# Half_Slave.net
KiCad netlist of a schematic drawn in Altium Designer
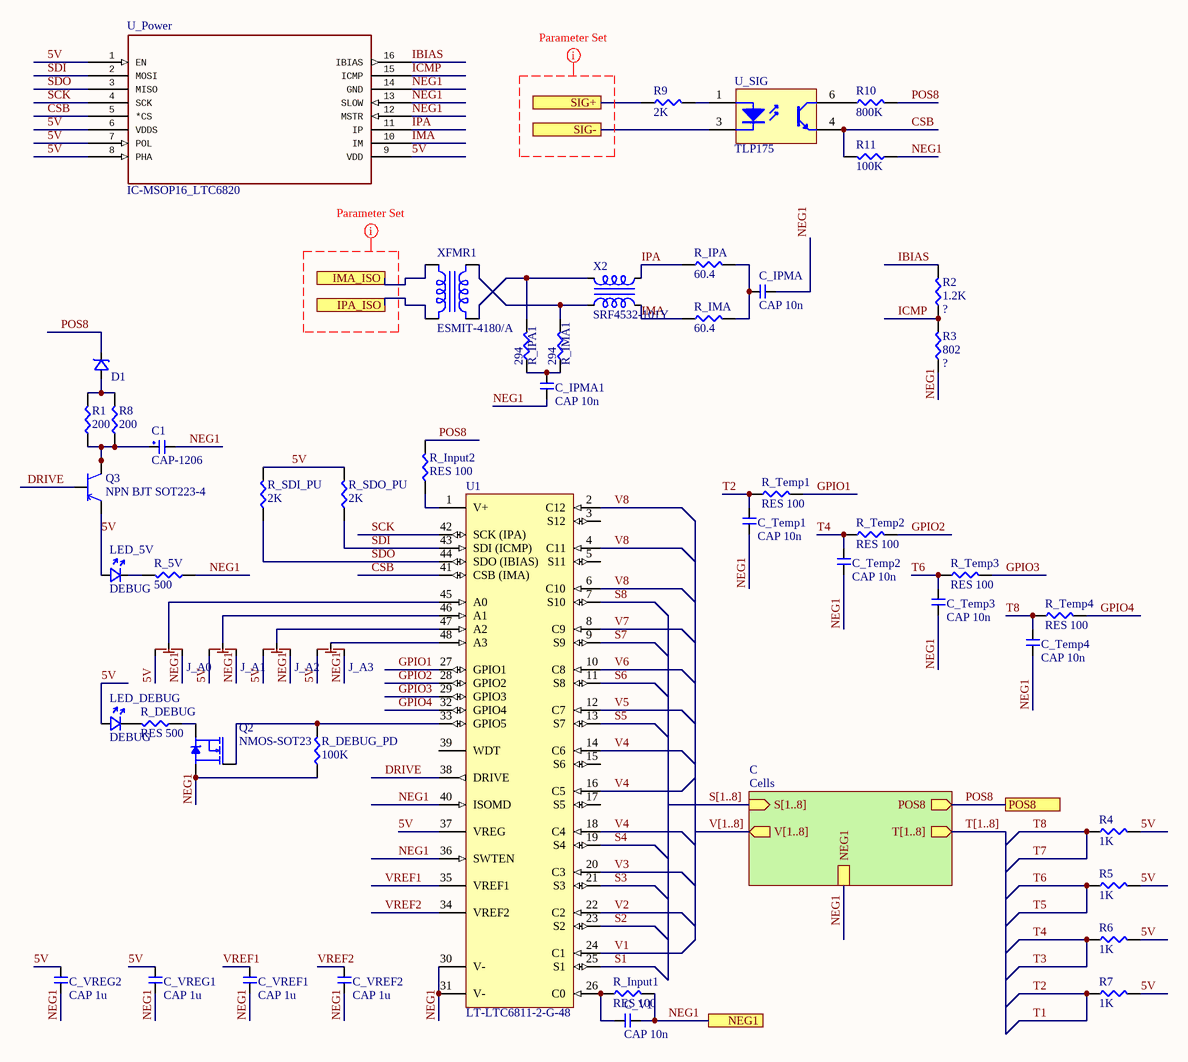
[diagram p0: Half_Slave.SchDoc]

(export (version "E")
  (design (tool "Eeschema 10.0.6"))
  (components
    (comp (ref "C1")
      (value "CAP-1206")
      (footprint "CAPCP3216X16N")
      (libsource (lib "LTC6811") (part "CAP-1206"))
    )
    (comp (ref "C_IPMA")
      (value "CAP 10n")
      (footprint "CAP-0603")
      (description "CAP-0603")
      (libsource (lib "ife18_TS_BMS_LTC6813_v2_Library") (part "CAP-0603"))
    )
    (comp (ref "C_IPMA1")
      (value "CAP 10n")
      (footprint "CAP-0603")
      (description "CAP-0603")
      (libsource (lib "ife18_TS_BMS_LTC6813_v2_Library") (part "CAP-0603"))
    )
    (comp (ref "C_Temp1")
      (value "CAP 10n")
      (footprint "CAP-0603")
      (description "CAP-0603")
      (libsource (lib "altium-import") (part "root_1_CAP-0603_"))
    )
    (comp (ref "C_Temp2")
      (value "CAP 10n")
      (footprint "CAP-0603")
      (description "CAP-0603")
      (libsource (lib "altium-import") (part "root_1_CAP-0603_"))
    )
    (comp (ref "C_Temp3")
      (value "CAP 10n")
      (footprint "CAP-0603")
      (description "CAP-0603")
      (libsource (lib "altium-import") (part "root_1_CAP-0603_"))
    )
    (comp (ref "C_Temp4")
      (value "CAP 10n")
      (footprint "CAP-0603")
      (description "CAP-0603")
      (libsource (lib "altium-import") (part "root_1_CAP-0603_"))
    )
    (comp (ref "C_V1")
      (value "CAP 10n")
      (footprint "CAP-0603")
      (description "CAP-0603")
      (libsource (lib "altium-import") (part "root_2_CAP-0603_"))
    )
    (comp (ref "C_VREF1")
      (value "CAP 1u")
      (footprint "CAP-0603")
      (description "CAP-0603")
      (libsource (lib "altium-import") (part "root_1_CAP-0603_"))
    )
    (comp (ref "C_VREF2")
      (value "CAP 1u")
      (footprint "CAP-0603")
      (description "CAP-0603")
      (libsource (lib "altium-import") (part "root_1_CAP-0603_"))
    )
    (comp (ref "C_VREG1")
      (value "CAP 1u")
      (footprint "CAP-0603")
      (description "CAP-0603")
      (libsource (lib "altium-import") (part "root_1_CAP-0603_"))
    )
    (comp (ref "C_VREG2")
      (value "CAP 1u")
      (footprint "CAP-0603")
      (description "CAP-0603")
      (libsource (lib "altium-import") (part "root_1_CAP-0603_"))
    )
    (comp (ref "D1") (value "?") (footprint "SMB") (libsource (lib "ife19_Elec_Library") (part "DIODE-SMB")))
    (comp (ref "J_A0")
      (value "DPDT Solder Jumper")
      (footprint "DPDT Solder")
      (libsource (lib "LTC6811") (part "DPDT Solder"))
    )
    (comp (ref "J_A1")
      (value "DPDT Solder Jumper")
      (footprint "DPDT Solder")
      (libsource (lib "LTC6811") (part "DPDT Solder"))
    )
    (comp (ref "J_A2")
      (value "DPDT Solder Jumper")
      (footprint "DPDT Solder")
      (libsource (lib "LTC6811") (part "DPDT Solder"))
    )
    (comp (ref "J_A3")
      (value "DPDT Solder Jumper")
      (footprint "DPDT Solder")
      (libsource (lib "LTC6811") (part "DPDT Solder"))
    )
    (comp (ref "LED_5V")
      (value "DEBUG")
      (footprint "LED-0603")
      (description "LED-0603")
      (libsource (lib "altium-import") (part "root_0_LED-0603_"))
    )
    (comp (ref "LED_DEBUG")
      (value "DEBUG")
      (footprint "LED-0603")
      (description "LED-0603")
      (libsource (lib "altium-import") (part "root_0_LED-0603_"))
    )
    (comp (ref "Q2")
      (value "NMOS-SOT23")
      (footprint "SOT23")
      (libsource (lib "ife19_Elec_Library") (part "NMOS-SOT23"))
    )
    (comp (ref "Q3")
      (value "NPN BJT SOT223-4")
      (footprint "SOT223")
      (description "BCP54,115")
      (libsource (lib "ife19_Elec_Library") (part "NPN_SOT223-4"))
    )
    (comp (ref "R1")
      (value "200")
      (footprint "RES-0603")
      (libsource (lib "ife18_TS_BMS_LTC6813_v2_Library") (part "RES-0603"))
    )
    (comp (ref "R2")
      (value "1.2K")
      (footprint "RES-0603")
      (description "RES SMD 0603")
      (fields (field (name "PART") "RES_0603") (field (name "ALTIUM_VALUE") "?"))
      (libsource (lib "IFE") (part "RES"))
    )
    (comp (ref "R3")
      (value "802")
      (footprint "RES-0603")
      (description "RES SMD 0603")
      (fields (field (name "PART") "RES_0603") (field (name "ALTIUM_VALUE") "?"))
      (libsource (lib "IFE") (part "RES"))
    )
    (comp (ref "R4")
      (value "1K")
      (footprint "RES-0603")
      (libsource (lib "ife19_Elec_Library") (part "RES-0603"))
    )
    (comp (ref "R5")
      (value "1K")
      (footprint "RES-0603")
      (libsource (lib "ife19_Elec_Library") (part "RES-0603"))
    )
    (comp (ref "R6")
      (value "1K")
      (footprint "RES-0603")
      (libsource (lib "ife19_Elec_Library") (part "RES-0603"))
    )
    (comp (ref "R7")
      (value "1K")
      (footprint "RES-0603")
      (libsource (lib "ife19_Elec_Library") (part "RES-0603"))
    )
    (comp (ref "R8")
      (value "200")
      (footprint "RES-0603")
      (libsource (lib "ife18_TS_BMS_LTC6813_v2_Library") (part "RES-0603"))
    )
    (comp (ref "R9")
      (value "2K")
      (footprint "RES-0603")
      (libsource (lib "ife19_Elec_Library") (part "RES-0603"))
    )
    (comp (ref "R10")
      (value "800K")
      (footprint "RES-0603")
      (libsource (lib "ife19_Elec_Library") (part "RES-0603"))
    )
    (comp (ref "R11")
      (value "100K")
      (footprint "RES-0603")
      (libsource (lib "ife19_Elec_Library") (part "RES-0603"))
    )
    (comp (ref "R_5V")
      (value "500")
      (footprint "RES-0603")
      (libsource (lib "altium-import") (part "root_2_RES-0603_"))
    )
    (comp (ref "R_DEBUG")
      (value "RES 500")
      (footprint "RES-0603")
      (libsource (lib "altium-import") (part "root_2_RES-0603_"))
    )
    (comp (ref "R_DEBUG_PD")
      (value "100K")
      (footprint "RES-0603")
      (libsource (lib "ife18_TS_BMS_LTC6813_v2_Library") (part "RES-0603"))
    )
    (comp (ref "R_IMA")
      (value "60.4")
      (footprint "RES-0603")
      (libsource (lib "ife18_TS_BMS_LTC6813_v2_Library") (part "RES-0603"))
    )
    (comp (ref "R_IMA1")
      (value "294")
      (footprint "RES-0603")
      (libsource (lib "ife18_TS_BMS_LTC6813_v2_Library") (part "RES-0603"))
    )
    (comp (ref "R_Input1")
      (value "RES 100")
      (footprint "RES-0603")
      (libsource (lib "altium-import") (part "root_0_RES-0603_"))
    )
    (comp (ref "R_Input2")
      (value "RES 100")
      (footprint "RES-0603")
      (libsource (lib "altium-import") (part "root_1_RES-0603_"))
    )
    (comp (ref "R_IPA")
      (value "60.4")
      (footprint "RES-0603")
      (libsource (lib "ife18_TS_BMS_LTC6813_v2_Library") (part "RES-0603"))
    )
    (comp (ref "R_IPA1")
      (value "294")
      (footprint "RES-0603")
      (libsource (lib "ife18_TS_BMS_LTC6813_v2_Library") (part "RES-0603"))
    )
    (comp (ref "R_SDI_PU")
      (value "2K")
      (footprint "RES-0603")
      (libsource (lib "ife18_TS_BMS_LTC6813_v2_Library") (part "RES-0603"))
    )
    (comp (ref "R_SDO_PU")
      (value "2K")
      (footprint "RES-0603")
      (libsource (lib "ife18_TS_BMS_LTC6813_v2_Library") (part "RES-0603"))
    )
    (comp (ref "R_Temp1")
      (value "RES 100")
      (footprint "RES-0603")
      (libsource (lib "altium-import") (part "root_0_RES-0603_"))
    )
    (comp (ref "R_Temp2")
      (value "RES 100")
      (footprint "RES-0603")
      (libsource (lib "altium-import") (part "root_0_RES-0603_"))
    )
    (comp (ref "R_Temp3")
      (value "RES 100")
      (footprint "RES-0603")
      (libsource (lib "altium-import") (part "root_0_RES-0603_"))
    )
    (comp (ref "R_Temp4")
      (value "RES 100")
      (footprint "RES-0603")
      (libsource (lib "altium-import") (part "root_0_RES-0603_"))
    )
    (comp (ref "U1")
      (value "LT-LTC6811-2-G-48")
      (footprint "SSOP-48N")
      (libsource (lib "LTC6811") (part "LT-LTC6811-2-G-48"))
    )
    (comp (ref "U_Power")
      (value "IC-MSOP16_LTC6820")
      (footprint "MSOP16")
      (libsource (lib "ife19_Elec_Library") (part "IC-MSOP16_LTC6820"))
    )
    (comp (ref "U_SIG")
      (value "TLP175")
      (footprint "TOSH-11-4C1_N")
      (fields (field (name "MANUFACTURER") "Toshiba"))
      (libsource (lib "Altium Content Vault") (part "TOSH-TLP181-SOP-4"))
    )
    (comp (ref "X2")
      (value "SRF4532-101Y")
      (footprint "SRF4532")
      (libsource (lib "ife19_Elec_Library") (part "CMC_SRF4532"))
    )
    (comp (ref "XFMR1")
      (value "ESMIT-4180/A")
      (footprint "ISOXFMR_ESMIT4180")
      (libsource (lib "ife19_Elec_Library") (part "ISOXFMR_ESMIT4180"))
    )
  )
  (nets
    (net (code "1") (name "/5V") (class "Default")
      (node (ref "C_VREG1") (pin "2") (pinfunction "2_2") (pintype "passive"))
      (node (ref "C_VREG2") (pin "2") (pinfunction "2_2") (pintype "passive"))
      (node (ref "J_A0") (pin "2") (pintype "passive"))
      (node (ref "J_A1") (pin "2") (pintype "passive"))
      (node (ref "J_A2") (pin "2") (pintype "passive"))
      (node (ref "J_A3") (pin "2") (pintype "passive"))
      (node (ref "LED_5V") (pin "A") (pinfunction "A_A") (pintype "passive"))
      (node (ref "LED_DEBUG") (pin "A") (pinfunction "A_A") (pintype "passive"))
      (node (ref "Q3") (pin "3") (pinfunction "E_3") (pintype "passive"))
      (node (ref "R4") (pin "2") (pinfunction "2_2") (pintype "passive"))
      (node (ref "R5") (pin "2") (pinfunction "2_2") (pintype "passive"))
      (node (ref "R6") (pin "2") (pinfunction "2_2") (pintype "passive"))
      (node (ref "R7") (pin "2") (pinfunction "2_2") (pintype "passive"))
      (node (ref "R_SDI_PU") (pin "2") (pinfunction "2_2") (pintype "passive"))
      (node (ref "R_SDO_PU") (pin "2") (pinfunction "2_2") (pintype "passive"))
      (node (ref "U1") (pin "37") (pinfunction "VREG_37") (pintype "power_in"))
      (node (ref "U_Power") (pin "1") (pinfunction "EN_1") (pintype "input"))
      (node (ref "U_Power") (pin "6") (pinfunction "VDDS_6") (pintype "power_in"))
      (node (ref "U_Power") (pin "7") (pinfunction "POL_7") (pintype "input"))
      (node (ref "U_Power") (pin "8") (pinfunction "PHA_8") (pintype "input"))
      (node (ref "U_Power") (pin "9") (pinfunction "VDD_9") (pintype "power_in"))
    )
    (net (code "2") (name "/CSB") (class "Default")
      (node (ref "R11") (pin "2") (pinfunction "2_2") (pintype "passive"))
      (node (ref "U1") (pin "41") (pinfunction "CSB_(IMA)_41") (pintype "bidirectional"))
      (node (ref "U_Power") (pin "5") (pinfunction "*CS_5") (pintype "passive"))
      (node (ref "U_SIG") (pin "4") (pinfunction "EMITTER_4") (pintype "passive"))
    )
    (net (code "3") (name "/DRIVE") (class "Default")
      (node (ref "Q3") (pin "1") (pinfunction "B_1") (pintype "passive"))
      (node (ref "U1") (pin "38") (pinfunction "DRIVE_38") (pintype "output"))
    )
    (net (code "4") (name "/GPIO1") (class "Default")
      (node (ref "R_Temp1") (pin "2") (pinfunction "2_2") (pintype "passive"))
      (node (ref "U1") (pin "27") (pinfunction "GPIO1_27") (pintype "bidirectional"))
    )
    (net (code "5") (name "/GPIO2") (class "Default")
      (node (ref "R_Temp2") (pin "2") (pinfunction "2_2") (pintype "passive"))
      (node (ref "U1") (pin "28") (pinfunction "GPIO2_28") (pintype "bidirectional"))
    )
    (net (code "6") (name "/GPIO3") (class "Default")
      (node (ref "R_Temp3") (pin "2") (pinfunction "2_2") (pintype "passive"))
      (node (ref "U1") (pin "29") (pinfunction "GPIO3_29") (pintype "bidirectional"))
    )
    (net (code "7") (name "/GPIO4") (class "Default")
      (node (ref "R_Temp4") (pin "2") (pinfunction "2_2") (pintype "passive"))
      (node (ref "U1") (pin "32") (pinfunction "GPIO4_32") (pintype "bidirectional"))
    )
    (net (code "8") (name "/IBIAS") (class "Default")
      (node (ref "R2") (pin "2") (pinfunction "2_2") (pintype "passive"))
      (node (ref "U_Power") (pin "16") (pinfunction "IBIAS_16") (pintype "output"))
    )
    (net (code "9") (name "/ICMP") (class "Default")
      (node (ref "R2") (pin "1") (pinfunction "1_1") (pintype "passive"))
      (node (ref "R3") (pin "2") (pinfunction "2_2") (pintype "passive"))
      (node (ref "U_Power") (pin "15") (pinfunction "ICMP_15") (pintype "passive"))
    )
    (net (code "10") (name "/IMA") (class "Default")
      (node (ref "R_IMA") (pin "2") (pinfunction "2_2") (pintype "passive"))
      (node (ref "U_Power") (pin "10") (pinfunction "IM_10") (pintype "passive"))
      (node (ref "X2") (pin "4") (pinfunction "4_4") (pintype "passive"))
    )
    (net (code "11") (name "/IMA_ISO") (class "Default")
      (node (ref "XFMR1") (pin "2") (pinfunction "2_2") (pintype "passive"))
    )
    (net (code "12") (name "/IPA") (class "Default")
      (node (ref "R_IPA") (pin "2") (pinfunction "2_2") (pintype "passive"))
      (node (ref "U_Power") (pin "11") (pinfunction "IP_11") (pintype "passive"))
      (node (ref "X2") (pin "1") (pinfunction "1_1") (pintype "passive"))
    )
    (net (code "13") (name "/IPA_ISO") (class "Default")
      (node (ref "XFMR1") (pin "1") (pinfunction "1_1") (pintype "passive"))
    )
    (net (code "14") (name "/NEG1") (class "Default")
      (node (ref "C1") (pin "2") (pinfunction "2_2") (pintype "passive"))
      (node (ref "C_IPMA") (pin "1") (pinfunction "1_1") (pintype "passive"))
      (node (ref "C_IPMA1") (pin "1") (pinfunction "1_1") (pintype "passive"))
      (node (ref "C_Temp1") (pin "1") (pinfunction "1_1") (pintype "passive"))
      (node (ref "C_Temp2") (pin "1") (pinfunction "1_1") (pintype "passive"))
      (node (ref "C_Temp3") (pin "1") (pinfunction "1_1") (pintype "passive"))
      (node (ref "C_Temp4") (pin "1") (pinfunction "1_1") (pintype "passive"))
      (node (ref "C_V1") (pin "1") (pinfunction "1_1") (pintype "passive"))
      (node (ref "C_VREF1") (pin "1") (pinfunction "1_1") (pintype "passive"))
      (node (ref "C_VREF2") (pin "1") (pinfunction "1_1") (pintype "passive"))
      (node (ref "C_VREG1") (pin "1") (pinfunction "1_1") (pintype "passive"))
      (node (ref "C_VREG2") (pin "1") (pinfunction "1_1") (pintype "passive"))
      (node (ref "J_A0") (pin "1") (pintype "passive"))
      (node (ref "J_A1") (pin "1") (pintype "passive"))
      (node (ref "J_A2") (pin "1") (pintype "passive"))
      (node (ref "J_A3") (pin "1") (pintype "passive"))
      (node (ref "Q2") (pin "2") (pinfunction "S_2") (pintype "passive"))
      (node (ref "R11") (pin "1") (pinfunction "1_1") (pintype "passive"))
      (node (ref "R3") (pin "1") (pinfunction "1_1") (pintype "passive"))
      (node (ref "R_5V") (pin "1") (pinfunction "1_1") (pintype "passive"))
      (node (ref "R_DEBUG_PD") (pin "1") (pinfunction "1_1") (pintype "passive"))
      (node (ref "R_Input1") (pin "2") (pinfunction "2_2") (pintype "passive"))
      (node (ref "U1") (pin "30") (pinfunction "V-_30") (pintype "power_in"))
      (node (ref "U1") (pin "31") (pinfunction "V-_31") (pintype "power_in"))
      (node (ref "U1") (pin "36") (pinfunction "SWTEN_36") (pintype "input"))
      (node (ref "U1") (pin "40") (pinfunction "ISOMD_40") (pintype "input"))
      (node (ref "U_Power") (pin "12") (pinfunction "MSTR_12") (pintype "input"))
      (node (ref "U_Power") (pin "13") (pinfunction "SLOW_13") (pintype "input"))
      (node (ref "U_Power") (pin "14") (pinfunction "GND_14") (pintype "power_in"))
    )
    (net (code "15") (name "/POS8") (class "Default")
      (node (ref "D1") (pin "K") (pinfunction "K_K") (pintype "passive"))
      (node (ref "R10") (pin "2") (pinfunction "2_2") (pintype "passive"))
      (node (ref "R_Input2") (pin "2") (pinfunction "2_2") (pintype "passive"))
    )
    (net (code "16") (name "/S1") (class "Default")
      (node (ref "U1") (pin "25") (pinfunction "S1_25") (pintype "bidirectional"))
    )
    (net (code "17") (name "/S2") (class "Default")
      (node (ref "U1") (pin "23") (pinfunction "S2_23") (pintype "bidirectional"))
    )
    (net (code "18") (name "/S3") (class "Default")
      (node (ref "U1") (pin "21") (pinfunction "S3_21") (pintype "bidirectional"))
    )
    (net (code "19") (name "/S4") (class "Default")
      (node (ref "U1") (pin "19") (pinfunction "S4_19") (pintype "bidirectional"))
    )
    (net (code "20") (name "/S5") (class "Default")
      (node (ref "U1") (pin "13") (pinfunction "S7_13") (pintype "bidirectional"))
    )
    (net (code "21") (name "/S6") (class "Default")
      (node (ref "U1") (pin "11") (pinfunction "S8_11") (pintype "bidirectional"))
    )
    (net (code "22") (name "/S7") (class "Default")
      (node (ref "U1") (pin "9") (pinfunction "S9_9") (pintype "bidirectional"))
    )
    (net (code "23") (name "/S8") (class "Default")
      (node (ref "U1") (pin "7") (pinfunction "S10_7") (pintype "bidirectional"))
    )
    (net (code "24") (name "/SCK") (class "Default")
      (node (ref "U1") (pin "42") (pinfunction "SCK_(IPA)_42") (pintype "bidirectional"))
      (node (ref "U_Power") (pin "4") (pinfunction "SCK_4") (pintype "passive"))
    )
    (net (code "25") (name "/SDI") (class "Default")
      (node (ref "R_SDO_PU") (pin "1") (pinfunction "1_1") (pintype "passive"))
      (node (ref "U1") (pin "43") (pinfunction "SDI_(ICMP)_43") (pintype "input"))
      (node (ref "U_Power") (pin "2") (pinfunction "MOSI_2") (pintype "passive"))
    )
    (net (code "26") (name "/SDO") (class "Default")
      (node (ref "R_SDI_PU") (pin "1") (pinfunction "1_1") (pintype "passive"))
      (node (ref "U1") (pin "44") (pinfunction "SDO_(IBIAS)_44") (pintype "bidirectional"))
      (node (ref "U_Power") (pin "3") (pinfunction "MISO_3") (pintype "passive"))
    )
    (net (code "27") (name "/SIG+") (class "Default")
      (node (ref "R9") (pin "1") (pinfunction "1_1") (pintype "passive"))
    )
    (net (code "28") (name "/SIG-") (class "Default")
      (node (ref "U_SIG") (pin "3") (pinfunction "CATHODE_3") (pintype "passive"))
    )
    (net (code "30") (name "/T2") (class "Default")
      (node (ref "C_Temp1") (pin "2") (pinfunction "2_2") (pintype "passive"))
      (node (ref "R7") (pin "1") (pinfunction "1_1") (pintype "passive"))
      (node (ref "R_Temp1") (pin "1") (pinfunction "1_1") (pintype "passive"))
    )
    (net (code "31") (name "/T4") (class "Default")
      (node (ref "C_Temp2") (pin "2") (pinfunction "2_2") (pintype "passive"))
      (node (ref "R6") (pin "1") (pinfunction "1_1") (pintype "passive"))
      (node (ref "R_Temp2") (pin "1") (pinfunction "1_1") (pintype "passive"))
    )
    (net (code "32") (name "/T6") (class "Default")
      (node (ref "C_Temp3") (pin "2") (pinfunction "2_2") (pintype "passive"))
      (node (ref "R5") (pin "1") (pinfunction "1_1") (pintype "passive"))
      (node (ref "R_Temp3") (pin "1") (pinfunction "1_1") (pintype "passive"))
    )
    (net (code "33") (name "/T8") (class "Default")
      (node (ref "C_Temp4") (pin "2") (pinfunction "2_2") (pintype "passive"))
      (node (ref "R4") (pin "1") (pinfunction "1_1") (pintype "passive"))
      (node (ref "R_Temp4") (pin "1") (pinfunction "1_1") (pintype "passive"))
    )
    (net (code "35") (name "/V1") (class "Default")
      (node (ref "U1") (pin "24") (pinfunction "C1_24") (pintype "input"))
    )
    (net (code "36") (name "/V2") (class "Default")
      (node (ref "U1") (pin "22") (pinfunction "C2_22") (pintype "input"))
    )
    (net (code "37") (name "/V3") (class "Default")
      (node (ref "U1") (pin "20") (pinfunction "C3_20") (pintype "input"))
    )
    (net (code "38") (name "/V4") (class "Default")
      (node (ref "U1") (pin "14") (pinfunction "C6_14") (pintype "input"))
      (node (ref "U1") (pin "16") (pinfunction "C5_16") (pintype "input"))
      (node (ref "U1") (pin "18") (pinfunction "C4_18") (pintype "input"))
    )
    (net (code "39") (name "/V5") (class "Default")
      (node (ref "U1") (pin "12") (pinfunction "C7_12") (pintype "input"))
    )
    (net (code "40") (name "/V6") (class "Default")
      (node (ref "U1") (pin "10") (pinfunction "C8_10") (pintype "input"))
    )
    (net (code "41") (name "/V7") (class "Default")
      (node (ref "U1") (pin "8") (pinfunction "C9_8") (pintype "input"))
    )
    (net (code "42") (name "/V8") (class "Default")
      (node (ref "U1") (pin "2") (pinfunction "C12_2") (pintype "input"))
      (node (ref "U1") (pin "4") (pinfunction "C11_4") (pintype "input"))
      (node (ref "U1") (pin "6") (pinfunction "C10_6") (pintype "input"))
    )
    (net (code "43") (name "/VREF1") (class "Default")
      (node (ref "C_VREF1") (pin "2") (pinfunction "2_2") (pintype "passive"))
      (node (ref "U1") (pin "35") (pinfunction "VREF1_35") (pintype "passive"))
    )
    (net (code "44") (name "/VREF2") (class "Default")
      (node (ref "C_VREF2") (pin "2") (pinfunction "2_2") (pintype "passive"))
      (node (ref "U1") (pin "34") (pinfunction "VREF2_34") (pintype "passive"))
    )
    (net (code "46") (name "Net-(C1-Pad1)") (class "Default")
      (node (ref "C1") (pin "1") (pinfunction "1_1") (pintype "passive"))
      (node (ref "Q3") (pin "2") (pinfunction "C_2") (pintype "passive"))
      (node (ref "Q3") (pin "4") (pinfunction "C_4") (pintype "passive"))
      (node (ref "R1") (pin "1") (pinfunction "1_1") (pintype "passive"))
      (node (ref "R8") (pin "1") (pinfunction "1_1") (pintype "passive"))
    )
    (net (code "47") (name "Net-(C_IPMA-Pad2)") (class "Default")
      (node (ref "C_IPMA") (pin "2") (pinfunction "2_2") (pintype "passive"))
      (node (ref "R_IMA") (pin "1") (pinfunction "1_1") (pintype "passive"))
      (node (ref "R_IPA") (pin "1") (pinfunction "1_1") (pintype "passive"))
    )
    (net (code "48") (name "Net-(C_IPMA1-Pad2)") (class "Default")
      (node (ref "C_IPMA1") (pin "2") (pinfunction "2_2") (pintype "passive"))
      (node (ref "R_IMA1") (pin "1") (pinfunction "1_1") (pintype "passive"))
      (node (ref "R_IPA1") (pin "1") (pinfunction "1_1") (pintype "passive"))
    )
    (net (code "49") (name "Net-(D1-PadA)") (class "Default")
      (node (ref "D1") (pin "A") (pinfunction "A_A") (pintype "passive"))
      (node (ref "R1") (pin "2") (pinfunction "2_2") (pintype "passive"))
      (node (ref "R8") (pin "2") (pinfunction "2_2") (pintype "passive"))
    )
    (net (code "50") (name "Net-(LED_5V-PadK)") (class "Default")
      (node (ref "LED_5V") (pin "K") (pinfunction "K_K") (pintype "passive"))
      (node (ref "R_5V") (pin "2") (pinfunction "2_2") (pintype "passive"))
    )
    (net (code "51") (name "Net-(LED_DEBUG-PadK)") (class "Default")
      (node (ref "LED_DEBUG") (pin "K") (pinfunction "K_K") (pintype "passive"))
      (node (ref "R_DEBUG") (pin "2") (pinfunction "2_2") (pintype "passive"))
    )
    (net (code "52") (name "Net-(Q2-D)") (class "Default")
      (node (ref "Q2") (pin "3") (pinfunction "D_3") (pintype "passive"))
      (node (ref "R_DEBUG") (pin "1") (pinfunction "1_1") (pintype "passive"))
    )
    (net (code "53") (name "Net-(Q2-G)") (class "Default")
      (node (ref "Q2") (pin "1") (pinfunction "G_1") (pintype "passive"))
      (node (ref "R_DEBUG_PD") (pin "2") (pinfunction "2_2") (pintype "passive"))
      (node (ref "U1") (pin "33") (pinfunction "GPIO5_33") (pintype "bidirectional"))
    )
    (net (code "54") (name "Net-(R_IMA1-Pad2)") (class "Default")
      (node (ref "R_IMA1") (pin "2") (pinfunction "2_2") (pintype "passive"))
      (node (ref "X2") (pin "3") (pinfunction "3_3") (pintype "passive"))
      (node (ref "XFMR1") (pin "3") (pinfunction "3_3") (pintype "passive"))
    )
    (net (code "55") (name "Net-(R_IPA1-Pad2)") (class "Default")
      (node (ref "R_IPA1") (pin "2") (pinfunction "2_2") (pintype "passive"))
      (node (ref "X2") (pin "2") (pinfunction "2_2") (pintype "passive"))
      (node (ref "XFMR1") (pin "4") (pinfunction "4_4") (pintype "passive"))
    )
    (net (code "56") (name "Net-(U1-A0)") (class "Default")
      (node (ref "J_A0") (pin "3") (pintype "passive"))
      (node (ref "U1") (pin "45") (pinfunction "A0_45") (pintype "input"))
    )
    (net (code "57") (name "Net-(U1-A1)") (class "Default")
      (node (ref "J_A1") (pin "3") (pintype "passive"))
      (node (ref "U1") (pin "46") (pinfunction "A1_46") (pintype "input"))
    )
    (net (code "58") (name "Net-(U1-A2)") (class "Default")
      (node (ref "J_A2") (pin "3") (pintype "passive"))
      (node (ref "U1") (pin "47") (pinfunction "A2_47") (pintype "input"))
    )
    (net (code "59") (name "Net-(U1-A3)") (class "Default")
      (node (ref "J_A3") (pin "3") (pintype "passive"))
      (node (ref "U1") (pin "48") (pinfunction "A3_48") (pintype "input"))
    )
    (net (code "60") (name "Net-(U1-C0)") (class "Default")
      (node (ref "C_V1") (pin "2") (pinfunction "2_2") (pintype "passive"))
      (node (ref "R_Input1") (pin "1") (pinfunction "1_1") (pintype "passive"))
      (node (ref "U1") (pin "26") (pinfunction "C0_26") (pintype "input"))
    )
    (net (code "61") (name "Net-(U1-V+)") (class "Default")
      (node (ref "R_Input2") (pin "1") (pinfunction "1_1") (pintype "passive"))
      (node (ref "U1") (pin "1") (pinfunction "V+_1") (pintype "power_in"))
    )
    (net (code "62") (name "Net-(U_SIG-ANODE)") (class "Default")
      (node (ref "R9") (pin "2") (pinfunction "2_2") (pintype "passive"))
      (node (ref "U_SIG") (pin "1") (pinfunction "ANODE_1") (pintype "passive"))
    )
    (net (code "63") (name "Net-(U_SIG-COLLECTOR)") (class "Default")
      (node (ref "R10") (pin "1") (pinfunction "1_1") (pintype "passive"))
      (node (ref "U_SIG") (pin "6") (pinfunction "COLLECTOR_6") (pintype "passive"))
    )
    (net (code "64") (name "unconnected-(U1-S5-Pad17)") (class "Default")
      (node (ref "U1") (pin "17") (pinfunction "S5_17") (pintype "bidirectional"))
    )
    (net (code "65") (name "unconnected-(U1-S6-Pad15)") (class "Default")
      (node (ref "U1") (pin "15") (pinfunction "S6_15") (pintype "bidirectional"))
    )
    (net (code "66") (name "unconnected-(U1-S11-Pad5)") (class "Default")
      (node (ref "U1") (pin "5") (pinfunction "S11_5") (pintype "bidirectional"))
    )
    (net (code "67") (name "unconnected-(U1-S12-Pad3)") (class "Default")
      (node (ref "U1") (pin "3") (pinfunction "S12_3") (pintype "bidirectional"))
    )
    (net (code "68") (name "unconnected-(U1-WDT-Pad39)") (class "Default")
      (node (ref "U1") (pin "39") (pinfunction "WDT_39") (pintype "tri_state"))
    )
  )
)
